# CartePuissance.net
KiCad netlist of a schematic drawn in Altium Designer
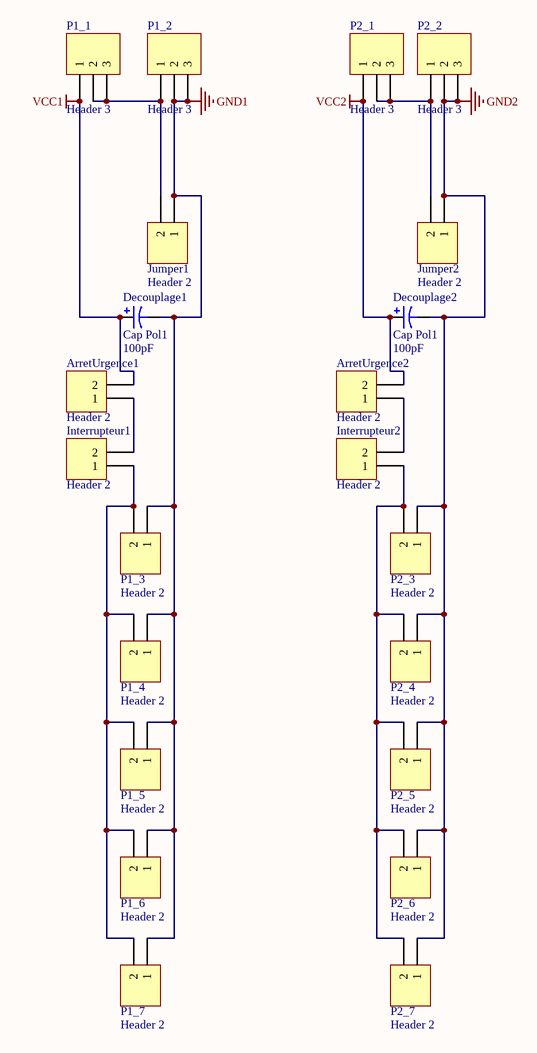
[diagram p0: CartePuissance.SchDoc]

(export (version "E")
  (design (tool "Eeschema 10.0.6"))
  (components
    (comp (ref "ArretUrgence1")
      (value "Header 2")
      (footprint "HDR1X2")
      (description "Header, 2-Pin")
      (fields (field (name "PUBLISHER") "Altium Limited"))
      (libsource (lib "") (part "Header 2_1"))
    )
    (comp (ref "ArretUrgence2")
      (value "Header 2")
      (footprint "HDR1X2")
      (description "Header, 2-Pin")
      (fields (field (name "PUBLISHER") "Altium Limited"))
      (libsource (lib "") (part "Header 2_1"))
    )
    (comp (ref "Decouplage1")
      (value "Cap Pol1")
      (footprint "RB7.6-15")
      (description "Polarized Capacitor (Radial)")
      (fields (field (name "ALTIUM_VALUE") "100pF") (field (name "PUBLISHER") "Altium Limited"))
      (libsource (lib "Miscellaneous Devices") (part "Cap Pol1"))
    )
    (comp (ref "Decouplage2")
      (value "Cap Pol1")
      (footprint "RB7.6-15")
      (description "Polarized Capacitor (Radial)")
      (fields (field (name "ALTIUM_VALUE") "100pF") (field (name "PUBLISHER") "Altium Limited"))
      (libsource (lib "Miscellaneous Devices") (part "Cap Pol1"))
    )
    (comp (ref "Interrupteur1")
      (value "Header 2")
      (footprint "HDR1X2")
      (description "Header, 2-Pin")
      (fields (field (name "PUBLISHER") "Altium Limited"))
      (libsource (lib "") (part "Header 2_1"))
    )
    (comp (ref "Interrupteur2")
      (value "Header 2")
      (footprint "HDR1X2")
      (description "Header, 2-Pin")
      (fields (field (name "PUBLISHER") "Altium Limited"))
      (libsource (lib "") (part "Header 2_1"))
    )
    (comp (ref "Jumper1")
      (value "Header 2")
      (footprint "HDR1X2")
      (description "Header, 2-Pin")
      (fields (field (name "PUBLISHER") "Altium Limited"))
      (libsource (lib "Miscellaneous Connectors") (part "Header 2"))
    )
    (comp (ref "Jumper2")
      (value "Header 2")
      (footprint "HDR1X2")
      (description "Header, 2-Pin")
      (fields (field (name "PUBLISHER") "Altium Limited"))
      (libsource (lib "Miscellaneous Connectors") (part "Header 2"))
    )
    (comp (ref "P1_1")
      (value "Header 3")
      (footprint "HDR1X3")
      (description "Header, 3-Pin")
      (fields (field (name "PUBLISHER") "Altium Limited"))
      (libsource (lib "Miscellaneous Connectors") (part "Header 3"))
    )
    (comp (ref "P1_2")
      (value "Header 3")
      (footprint "HDR1X3")
      (description "Header, 3-Pin")
      (fields (field (name "PUBLISHER") "Altium Limited"))
      (libsource (lib "Miscellaneous Connectors") (part "Header 3"))
    )
    (comp (ref "P1_3")
      (value "Header 2")
      (footprint "HDR1X2")
      (description "Header, 2-Pin")
      (fields (field (name "PUBLISHER") "Altium Limited"))
      (libsource (lib "Miscellaneous Connectors") (part "Header 2"))
    )
    (comp (ref "P1_4")
      (value "Header 2")
      (footprint "HDR1X2")
      (description "Header, 2-Pin")
      (fields (field (name "PUBLISHER") "Altium Limited"))
      (libsource (lib "Miscellaneous Connectors") (part "Header 2"))
    )
    (comp (ref "P1_5")
      (value "Header 2")
      (footprint "HDR1X2")
      (description "Header, 2-Pin")
      (fields (field (name "PUBLISHER") "Altium Limited"))
      (libsource (lib "Miscellaneous Connectors") (part "Header 2"))
    )
    (comp (ref "P1_6")
      (value "Header 2")
      (footprint "HDR1X2")
      (description "Header, 2-Pin")
      (fields (field (name "PUBLISHER") "Altium Limited"))
      (libsource (lib "Miscellaneous Connectors") (part "Header 2"))
    )
    (comp (ref "P1_7")
      (value "Header 2")
      (footprint "HDR1X2")
      (description "Header, 2-Pin")
      (fields (field (name "PUBLISHER") "Altium Limited"))
      (libsource (lib "Miscellaneous Connectors") (part "Header 2"))
    )
    (comp (ref "P2_1")
      (value "Header 3")
      (footprint "HDR1X3")
      (description "Header, 3-Pin")
      (fields (field (name "PUBLISHER") "Altium Limited"))
      (libsource (lib "Miscellaneous Connectors") (part "Header 3"))
    )
    (comp (ref "P2_2")
      (value "Header 3")
      (footprint "HDR1X3")
      (description "Header, 3-Pin")
      (fields (field (name "PUBLISHER") "Altium Limited"))
      (libsource (lib "Miscellaneous Connectors") (part "Header 3"))
    )
    (comp (ref "P2_3")
      (value "Header 2")
      (footprint "HDR1X2")
      (description "Header, 2-Pin")
      (fields (field (name "PUBLISHER") "Altium Limited"))
      (libsource (lib "Miscellaneous Connectors") (part "Header 2"))
    )
    (comp (ref "P2_4")
      (value "Header 2")
      (footprint "HDR1X2")
      (description "Header, 2-Pin")
      (fields (field (name "PUBLISHER") "Altium Limited"))
      (libsource (lib "Miscellaneous Connectors") (part "Header 2"))
    )
    (comp (ref "P2_5")
      (value "Header 2")
      (footprint "HDR1X2")
      (description "Header, 2-Pin")
      (fields (field (name "PUBLISHER") "Altium Limited"))
      (libsource (lib "Miscellaneous Connectors") (part "Header 2"))
    )
    (comp (ref "P2_6")
      (value "Header 2")
      (footprint "HDR1X2")
      (description "Header, 2-Pin")
      (fields (field (name "PUBLISHER") "Altium Limited"))
      (libsource (lib "Miscellaneous Connectors") (part "Header 2"))
    )
    (comp (ref "P2_7")
      (value "Header 2")
      (footprint "HDR1X2")
      (description "Header, 2-Pin")
      (fields (field (name "PUBLISHER") "Altium Limited"))
      (libsource (lib "Miscellaneous Connectors") (part "Header 2"))
    )
  )
  (nets
    (net (code "1") (name "GND1") (class "Default")
      (node (ref "Decouplage1") (pin "2") (pinfunction "2_2") (pintype "passive"))
      (node (ref "Jumper1") (pin "1") (pinfunction "1_1") (pintype "passive"))
      (node (ref "P1_2") (pin "2") (pinfunction "2_2") (pintype "passive"))
      (node (ref "P1_2") (pin "3") (pinfunction "3_3") (pintype "passive"))
      (node (ref "P1_3") (pin "1") (pinfunction "1_1") (pintype "passive"))
      (node (ref "P1_4") (pin "1") (pinfunction "1_1") (pintype "passive"))
      (node (ref "P1_5") (pin "1") (pinfunction "1_1") (pintype "passive"))
      (node (ref "P1_6") (pin "1") (pinfunction "1_1") (pintype "passive"))
      (node (ref "P1_7") (pin "1") (pinfunction "1_1") (pintype "passive"))
    )
    (net (code "2") (name "GND2") (class "Default")
      (node (ref "Decouplage2") (pin "2") (pinfunction "2_2") (pintype "passive"))
      (node (ref "Jumper2") (pin "1") (pinfunction "1_1") (pintype "passive"))
      (node (ref "P2_2") (pin "2") (pinfunction "2_2") (pintype "passive"))
      (node (ref "P2_2") (pin "3") (pinfunction "3_3") (pintype "passive"))
      (node (ref "P2_3") (pin "1") (pinfunction "1_1") (pintype "passive"))
      (node (ref "P2_4") (pin "1") (pinfunction "1_1") (pintype "passive"))
      (node (ref "P2_5") (pin "1") (pinfunction "1_1") (pintype "passive"))
      (node (ref "P2_6") (pin "1") (pinfunction "1_1") (pintype "passive"))
      (node (ref "P2_7") (pin "1") (pinfunction "1_1") (pintype "passive"))
    )
    (net (code "3") (name "Net-(ArretUrgence1-Pad1)") (class "Default")
      (node (ref "ArretUrgence1") (pin "1") (pinfunction "1_1") (pintype "passive"))
      (node (ref "Interrupteur1") (pin "2") (pinfunction "2_2") (pintype "passive"))
    )
    (net (code "4") (name "Net-(ArretUrgence2-Pad1)") (class "Default")
      (node (ref "ArretUrgence2") (pin "1") (pinfunction "1_1") (pintype "passive"))
      (node (ref "Interrupteur2") (pin "2") (pinfunction "2_2") (pintype "passive"))
    )
    (net (code "5") (name "Net-(Interrupteur1-Pad1)") (class "Default")
      (node (ref "Interrupteur1") (pin "1") (pinfunction "1_1") (pintype "passive"))
      (node (ref "P1_3") (pin "2") (pinfunction "2_2") (pintype "passive"))
      (node (ref "P1_4") (pin "2") (pinfunction "2_2") (pintype "passive"))
      (node (ref "P1_5") (pin "2") (pinfunction "2_2") (pintype "passive"))
      (node (ref "P1_6") (pin "2") (pinfunction "2_2") (pintype "passive"))
      (node (ref "P1_7") (pin "2") (pinfunction "2_2") (pintype "passive"))
    )
    (net (code "6") (name "Net-(Interrupteur2-Pad1)") (class "Default")
      (node (ref "Interrupteur2") (pin "1") (pinfunction "1_1") (pintype "passive"))
      (node (ref "P2_3") (pin "2") (pinfunction "2_2") (pintype "passive"))
      (node (ref "P2_4") (pin "2") (pinfunction "2_2") (pintype "passive"))
      (node (ref "P2_5") (pin "2") (pinfunction "2_2") (pintype "passive"))
      (node (ref "P2_6") (pin "2") (pinfunction "2_2") (pintype "passive"))
      (node (ref "P2_7") (pin "2") (pinfunction "2_2") (pintype "passive"))
    )
    (net (code "7") (name "Net-(Jumper1-Pad2)") (class "Default")
      (node (ref "Jumper1") (pin "2") (pinfunction "2_2") (pintype "passive"))
      (node (ref "P1_1") (pin "2") (pinfunction "2_2") (pintype "passive"))
      (node (ref "P1_1") (pin "3") (pinfunction "3_3") (pintype "passive"))
      (node (ref "P1_2") (pin "1") (pinfunction "1_1") (pintype "passive"))
    )
    (net (code "8") (name "Net-(Jumper2-Pad2)") (class "Default")
      (node (ref "Jumper2") (pin "2") (pinfunction "2_2") (pintype "passive"))
      (node (ref "P2_1") (pin "2") (pinfunction "2_2") (pintype "passive"))
      (node (ref "P2_1") (pin "3") (pinfunction "3_3") (pintype "passive"))
      (node (ref "P2_2") (pin "1") (pinfunction "1_1") (pintype "passive"))
    )
    (net (code "9") (name "VCC1") (class "Default")
      (node (ref "ArretUrgence1") (pin "2") (pinfunction "2_2") (pintype "passive"))
      (node (ref "Decouplage1") (pin "1") (pinfunction "1_1") (pintype "passive"))
      (node (ref "P1_1") (pin "1") (pinfunction "1_1") (pintype "passive"))
    )
    (net (code "10") (name "VCC2") (class "Default")
      (node (ref "ArretUrgence2") (pin "2") (pinfunction "2_2") (pintype "passive"))
      (node (ref "Decouplage2") (pin "1") (pinfunction "1_1") (pintype "passive"))
      (node (ref "P2_1") (pin "1") (pinfunction "1_1") (pintype "passive"))
    )
  )
)
